# Crystal_Filter_v2.net
KiCad netlist of a schematic drawn in EAGLE
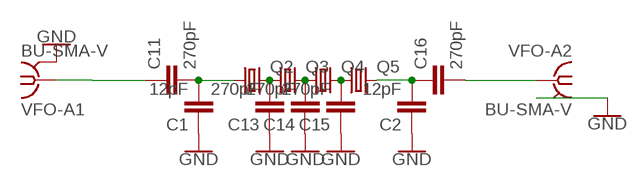
[diagram p0: schematic, sheet 1]

(export (version "E")
  (design (tool "Eeschema 10.0.6"))
  (components
    (comp (ref "C1")
      (value "12pF")
      (footprint "eagle-import:C5B3.5")
      (libsource (lib "eagle-import") (part "C5/3.5"))
    )
    (comp (ref "C2")
      (value "12pF")
      (footprint "eagle-import:C5B3.5")
      (libsource (lib "eagle-import") (part "C5/3.5"))
    )
    (comp (ref "C11")
      (value "270pF")
      (footprint "eagle-import:C5B3.5")
      (libsource (lib "eagle-import") (part "C5/3.5"))
    )
    (comp (ref "C13")
      (value "270pF")
      (footprint "eagle-import:C5B3.5")
      (libsource (lib "eagle-import") (part "C5/3.5"))
    )
    (comp (ref "C14")
      (value "270pF")
      (footprint "eagle-import:C5B3.5")
      (libsource (lib "eagle-import") (part "C5/3.5"))
    )
    (comp (ref "C15")
      (value "270pF")
      (footprint "eagle-import:C5B3.5")
      (libsource (lib "eagle-import") (part "C5/3.5"))
    )
    (comp (ref "C16")
      (value "270pF")
      (footprint "eagle-import:C5B3.5")
      (libsource (lib "eagle-import") (part "C5/3.5"))
    )
    (comp (ref "Q2")
      (value "CRYTALHC49S")
      (footprint "eagle-import:HC49_S")
      (libsource (lib "eagle-import") (part "CRYTALHC49S"))
    )
    (comp (ref "Q3")
      (value "CRYTALHC49S")
      (footprint "eagle-import:HC49_S")
      (libsource (lib "eagle-import") (part "CRYTALHC49S"))
    )
    (comp (ref "Q4")
      (value "CRYTALHC49S")
      (footprint "eagle-import:HC49_S")
      (libsource (lib "eagle-import") (part "CRYTALHC49S"))
    )
    (comp (ref "Q5")
      (value "CRYTALHC49S")
      (footprint "eagle-import:HC49_S")
      (libsource (lib "eagle-import") (part "CRYTALHC49S"))
    )
    (comp (ref "VFO-A1")
      (value "BU-SMA-V")
      (footprint "eagle-import:BU-SMA-V")
      (libsource (lib "eagle-import") (part "BU-SMA-V"))
    )
    (comp (ref "VFO-A2")
      (value "BU-SMA-V")
      (footprint "eagle-import:BU-SMA-V")
      (libsource (lib "eagle-import") (part "BU-SMA-V"))
    )
  )
  (nets
    (net (code "1") (name "GND") (class "Default")
      (node (ref "C1") (pin "1") (pinfunction "1_1") (pintype "passive"))
      (node (ref "C13") (pin "1") (pinfunction "1_1") (pintype "passive"))
      (node (ref "C14") (pin "1") (pinfunction "1_1") (pintype "passive"))
      (node (ref "C15") (pin "1") (pinfunction "1_1") (pintype "passive"))
      (node (ref "C2") (pin "1") (pinfunction "1_1") (pintype "passive"))
      (node (ref "VFO-A1") (pin "2") (pinfunction "2_2") (pintype "passive"))
      (node (ref "VFO-A1") (pin "3") (pinfunction "2_3") (pintype "passive"))
      (node (ref "VFO-A1") (pin "4") (pinfunction "2_4") (pintype "passive"))
      (node (ref "VFO-A1") (pin "5") (pinfunction "2_5") (pintype "passive"))
      (node (ref "VFO-A2") (pin "2") (pinfunction "2_2") (pintype "passive"))
      (node (ref "VFO-A2") (pin "3") (pinfunction "2_3") (pintype "passive"))
      (node (ref "VFO-A2") (pin "4") (pinfunction "2_4") (pintype "passive"))
      (node (ref "VFO-A2") (pin "5") (pinfunction "2_5") (pintype "passive"))
    )
    (net (code "2") (name "Net-(C1-Pad2)") (class "Default")
      (node (ref "C1") (pin "2") (pinfunction "2_2") (pintype "passive"))
      (node (ref "C11") (pin "2") (pinfunction "2_2") (pintype "passive"))
      (node (ref "Q2") (pin "1") (pinfunction "1_1") (pintype "passive"))
    )
    (net (code "3") (name "Net-(C11-Pad1)") (class "Default")
      (node (ref "C11") (pin "1") (pinfunction "1_1") (pintype "passive"))
      (node (ref "VFO-A1") (pin "1") (pinfunction "1_1") (pintype "passive"))
    )
    (net (code "4") (name "Net-(C13-Pad2)") (class "Default")
      (node (ref "C13") (pin "2") (pinfunction "2_2") (pintype "passive"))
      (node (ref "Q2") (pin "2") (pinfunction "2_2") (pintype "passive"))
      (node (ref "Q3") (pin "1") (pinfunction "1_1") (pintype "passive"))
    )
    (net (code "5") (name "Net-(C14-Pad2)") (class "Default")
      (node (ref "C14") (pin "2") (pinfunction "2_2") (pintype "passive"))
      (node (ref "Q3") (pin "2") (pinfunction "2_2") (pintype "passive"))
      (node (ref "Q4") (pin "1") (pinfunction "1_1") (pintype "passive"))
    )
    (net (code "6") (name "Net-(C15-Pad2)") (class "Default")
      (node (ref "C15") (pin "2") (pinfunction "2_2") (pintype "passive"))
      (node (ref "Q4") (pin "2") (pinfunction "2_2") (pintype "passive"))
      (node (ref "Q5") (pin "1") (pinfunction "1_1") (pintype "passive"))
    )
    (net (code "7") (name "Net-(C16-Pad1)") (class "Default")
      (node (ref "C16") (pin "1") (pinfunction "1_1") (pintype "passive"))
      (node (ref "C2") (pin "2") (pinfunction "2_2") (pintype "passive"))
      (node (ref "Q5") (pin "2") (pinfunction "2_2") (pintype "passive"))
    )
    (net (code "8") (name "Net-(C16-Pad2)") (class "Default")
      (node (ref "C16") (pin "2") (pinfunction "2_2") (pintype "passive"))
      (node (ref "VFO-A2") (pin "1") (pinfunction "1_1") (pintype "passive"))
    )
  )
)
